# design.net
KiCad netlist of a schematic drawn in Altium Designer
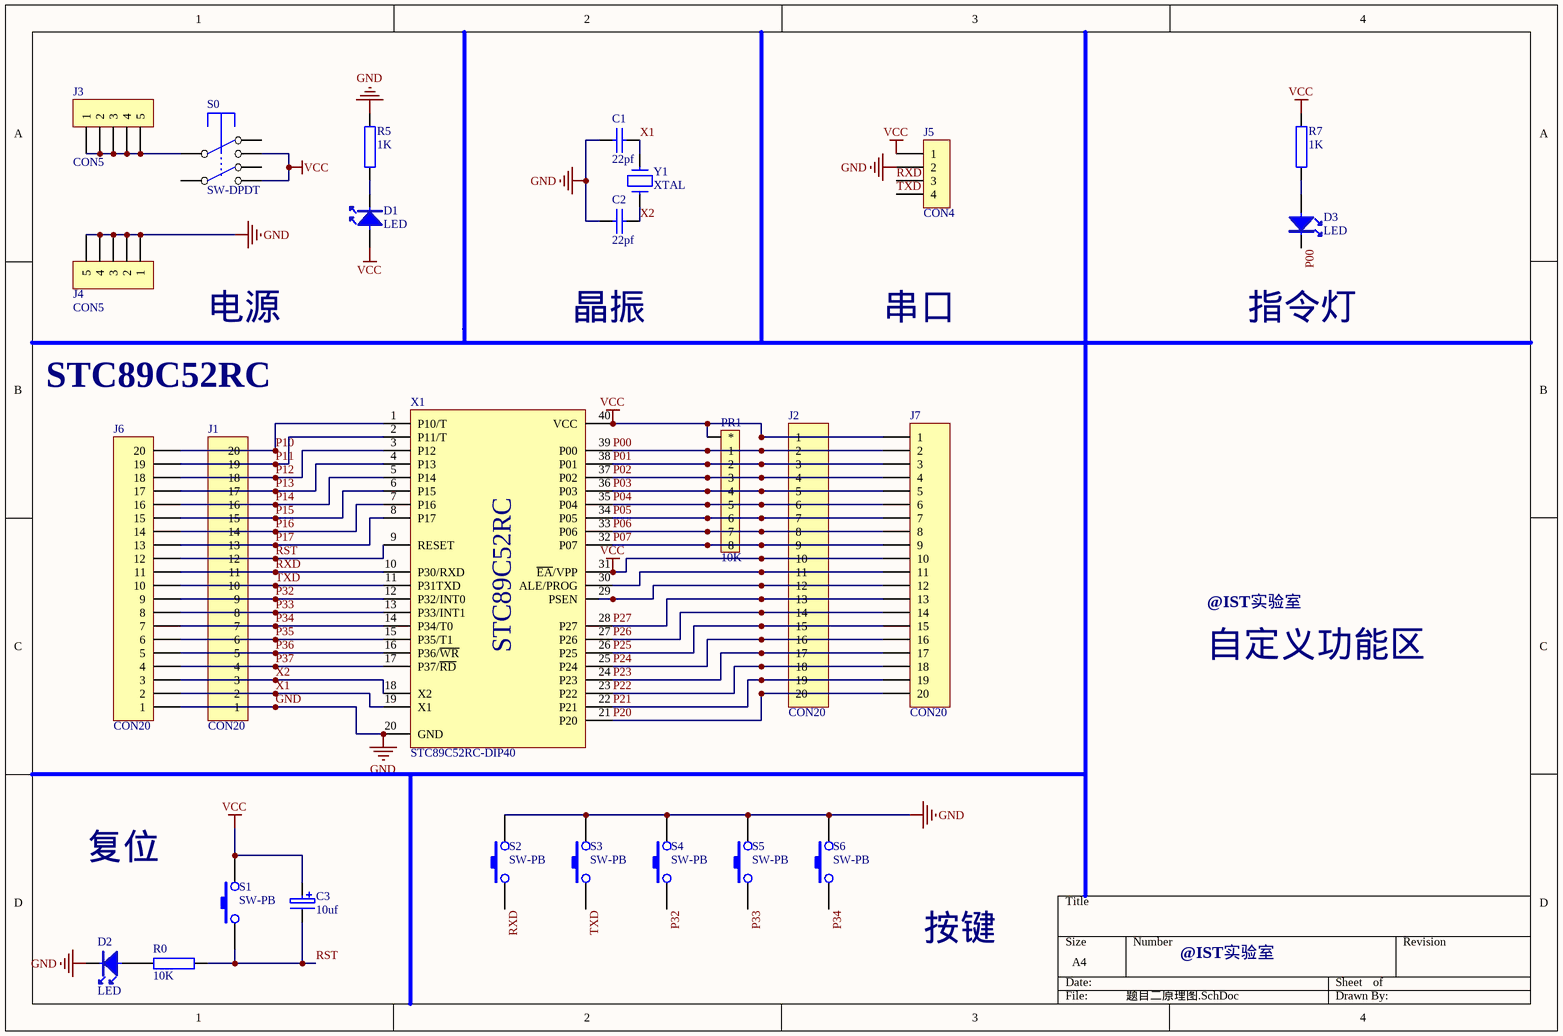
[diagram p0: 题目二原理图.SchDoc]

(export (version "E")
  (design (tool "Eeschema 10.0.6"))
  (components
    (comp (ref "C1") (value "22pf") (footprint "CAP2") (libsource (lib "51单片机集成库") (part "CAP1")))
    (comp (ref "C2") (value "22pf") (footprint "CAP2") (libsource (lib "51单片机集成库") (part "CAP1")))
    (comp (ref "C3") (value "10uf") (footprint "CAO1") (libsource (lib "51单片机集成库") (part "CAP3")))
    (comp (ref "D1") (value "LED") (footprint "LED2_B") (libsource (lib "51单片机集成库") (part "LED")))
    (comp (ref "D2") (value "LED") (footprint "LED2_B") (libsource (lib "51单片机集成库") (part "LED")))
    (comp (ref "D3") (value "LED") (footprint "LED2_B") (libsource (lib "51单片机集成库") (part "LED")))
    (comp (ref "J1")
      (value "CON20")
      (footprint "sip-20")
      (description "Connector")
      (libsource (lib "") (part "CON20_1"))
    )
    (comp (ref "J2")
      (value "CON20")
      (footprint "sip-20")
      (description "Connector")
      (libsource (lib "51单片机集成库") (part "CON20"))
    )
    (comp (ref "J3")
      (value "CON5")
      (footprint "sip-5")
      (description "Connector")
      (libsource (lib "51单片机集成库") (part "CON5"))
    )
    (comp (ref "J4")
      (value "CON5")
      (footprint "sip-5")
      (description "Connector")
      (libsource (lib "") (part "CON5_1"))
    )
    (comp (ref "J5")
      (value "CON4")
      (footprint "sip-4")
      (description "Connector")
      (libsource (lib "51单片机集成库") (part "CON4"))
    )
    (comp (ref "J6")
      (value "CON20")
      (footprint "sip-20")
      (description "Connector")
      (libsource (lib "") (part "CON20_1"))
    )
    (comp (ref "J7")
      (value "CON20")
      (footprint "sip-20")
      (description "Connector")
      (libsource (lib "51单片机集成库") (part "CON20"))
    )
    (comp (ref "PR1") (value "10K") (footprint "RP1") (libsource (lib "51单片机集成库") (part "PRES1")))
    (comp (ref "R0")
      (value "10K")
      (footprint "AXIAL0.4")
      (description "电阻")
      (libsource (lib "51单片机集成库") (part "RES"))
    )
    (comp (ref "R5")
      (value "1K")
      (footprint "AXIAL0.4")
      (description "电阻")
      (libsource (lib "51单片机集成库") (part "RES"))
    )
    (comp (ref "R7")
      (value "1K")
      (footprint "AXIAL0.4")
      (description "电阻")
      (libsource (lib "51单片机集成库") (part "RES"))
    )
    (comp (ref "S0") (value "SW-DPDT") (footprint "SWH7*7") (libsource (lib "51单片机集成库") (part "SW-DPDT")))
    (comp (ref "S1") (value "SW-PB") (footprint "SW6*6") (libsource (lib "51单片机集成库") (part "SW-PB")))
    (comp (ref "S2") (value "SW-PB") (footprint "SW6*6") (libsource (lib "51单片机集成库") (part "SW-PB")))
    (comp (ref "S3") (value "SW-PB") (footprint "SW6*6") (libsource (lib "51单片机集成库") (part "SW-PB")))
    (comp (ref "S4") (value "SW-PB") (footprint "SW6*6") (libsource (lib "51单片机集成库") (part "SW-PB")))
    (comp (ref "S5") (value "SW-PB") (footprint "SW6*6") (libsource (lib "51单片机集成库") (part "SW-PB")))
    (comp (ref "S6") (value "SW-PB") (footprint "SW6*6") (libsource (lib "51单片机集成库") (part "SW-PB")))
    (comp (ref "X1")
      (value "STC89C52RC-DIP40")
      (footprint "DIP-40")
      (libsource (lib "51单片机集成库") (part "STC89C52RC-DIP40"))
    )
    (comp (ref "Y1") (value "XTAL") (footprint "XTAL1") (libsource (lib "51单片机集成库") (part "CPY")))
  )
  (nets
    (net (code "1") (name "/P00") (class "Default")
      (node (ref "D3") (pin "2") (pinfunction "2_2") (pintype "passive"))
      (node (ref "J2") (pin "2") (pinfunction "2_2") (pintype "passive"))
      (node (ref "J7") (pin "2") (pinfunction "2_2") (pintype "passive"))
      (node (ref "PR1") (pin "2") (pinfunction "1_2") (pintype "passive"))
      (node (ref "X1") (pin "39") (pinfunction "P00_39") (pintype "passive"))
    )
    (net (code "2") (name "/P01") (class "Default")
      (node (ref "J2") (pin "3") (pinfunction "3_3") (pintype "passive"))
      (node (ref "J7") (pin "3") (pinfunction "3_3") (pintype "passive"))
      (node (ref "PR1") (pin "3") (pinfunction "2_3") (pintype "passive"))
      (node (ref "X1") (pin "38") (pinfunction "P01_38") (pintype "passive"))
    )
    (net (code "3") (name "/P02") (class "Default")
      (node (ref "J2") (pin "4") (pinfunction "4_4") (pintype "passive"))
      (node (ref "J7") (pin "4") (pinfunction "4_4") (pintype "passive"))
      (node (ref "PR1") (pin "4") (pinfunction "3_4") (pintype "passive"))
      (node (ref "X1") (pin "37") (pinfunction "P02_37") (pintype "passive"))
    )
    (net (code "4") (name "/P03") (class "Default")
      (node (ref "J2") (pin "5") (pinfunction "5_5") (pintype "passive"))
      (node (ref "J7") (pin "5") (pinfunction "5_5") (pintype "passive"))
      (node (ref "PR1") (pin "5") (pinfunction "4_5") (pintype "passive"))
      (node (ref "X1") (pin "36") (pinfunction "P03_36") (pintype "passive"))
    )
    (net (code "5") (name "/P04") (class "Default")
      (node (ref "J2") (pin "6") (pinfunction "6_6") (pintype "passive"))
      (node (ref "J7") (pin "6") (pinfunction "6_6") (pintype "passive"))
      (node (ref "PR1") (pin "6") (pinfunction "5_6") (pintype "passive"))
      (node (ref "X1") (pin "35") (pinfunction "P04_35") (pintype "passive"))
    )
    (net (code "6") (name "/P05") (class "Default")
      (node (ref "J2") (pin "7") (pinfunction "7_7") (pintype "passive"))
      (node (ref "J7") (pin "7") (pinfunction "7_7") (pintype "passive"))
      (node (ref "PR1") (pin "7") (pinfunction "6_7") (pintype "passive"))
      (node (ref "X1") (pin "34") (pinfunction "P05_34") (pintype "passive"))
    )
    (net (code "7") (name "/P06") (class "Default")
      (node (ref "J2") (pin "8") (pinfunction "8_8") (pintype "passive"))
      (node (ref "J7") (pin "8") (pinfunction "8_8") (pintype "passive"))
      (node (ref "PR1") (pin "8") (pinfunction "7_8") (pintype "passive"))
      (node (ref "X1") (pin "33") (pinfunction "P06_33") (pintype "passive"))
    )
    (net (code "8") (name "/P07") (class "Default")
      (node (ref "J2") (pin "9") (pinfunction "9_9") (pintype "passive"))
      (node (ref "J7") (pin "9") (pinfunction "9_9") (pintype "passive"))
      (node (ref "PR1") (pin "9") (pinfunction "8_9") (pintype "passive"))
      (node (ref "X1") (pin "32") (pinfunction "P07_32") (pintype "passive"))
    )
    (net (code "9") (name "/P10") (class "Default")
      (node (ref "J1") (pin "20") (pinfunction "20_20") (pintype "passive"))
      (node (ref "J6") (pin "20") (pinfunction "20_20") (pintype "passive"))
      (node (ref "X1") (pin "1") (pinfunction "P10/T_1") (pintype "passive"))
    )
    (net (code "10") (name "/P11") (class "Default")
      (node (ref "J1") (pin "19") (pinfunction "19_19") (pintype "passive"))
      (node (ref "J6") (pin "19") (pinfunction "19_19") (pintype "passive"))
      (node (ref "X1") (pin "2") (pinfunction "P11/T_2") (pintype "passive"))
    )
    (net (code "11") (name "/P12") (class "Default")
      (node (ref "J1") (pin "18") (pinfunction "18_18") (pintype "passive"))
      (node (ref "J6") (pin "18") (pinfunction "18_18") (pintype "passive"))
      (node (ref "X1") (pin "3") (pinfunction "P12_3") (pintype "passive"))
    )
    (net (code "12") (name "/P13") (class "Default")
      (node (ref "J1") (pin "17") (pinfunction "17_17") (pintype "passive"))
      (node (ref "J6") (pin "17") (pinfunction "17_17") (pintype "passive"))
      (node (ref "X1") (pin "4") (pinfunction "P13_4") (pintype "passive"))
    )
    (net (code "13") (name "/P14") (class "Default")
      (node (ref "J1") (pin "16") (pinfunction "16_16") (pintype "passive"))
      (node (ref "J6") (pin "16") (pinfunction "16_16") (pintype "passive"))
      (node (ref "X1") (pin "5") (pinfunction "P14_5") (pintype "passive"))
    )
    (net (code "14") (name "/P15") (class "Default")
      (node (ref "J1") (pin "15") (pinfunction "15_15") (pintype "passive"))
      (node (ref "J6") (pin "15") (pinfunction "15_15") (pintype "passive"))
      (node (ref "X1") (pin "6") (pinfunction "P15_6") (pintype "passive"))
    )
    (net (code "15") (name "/P16") (class "Default")
      (node (ref "J1") (pin "14") (pinfunction "14_14") (pintype "passive"))
      (node (ref "J6") (pin "14") (pinfunction "14_14") (pintype "passive"))
      (node (ref "X1") (pin "7") (pinfunction "P16_7") (pintype "passive"))
    )
    (net (code "16") (name "/P17") (class "Default")
      (node (ref "J1") (pin "13") (pinfunction "13_13") (pintype "passive"))
      (node (ref "J6") (pin "13") (pinfunction "13_13") (pintype "passive"))
      (node (ref "X1") (pin "8") (pinfunction "P17_8") (pintype "passive"))
    )
    (net (code "17") (name "/P20") (class "Default")
      (node (ref "J2") (pin "20") (pinfunction "20_20") (pintype "passive"))
      (node (ref "J7") (pin "20") (pinfunction "20_20") (pintype "passive"))
      (node (ref "X1") (pin "21") (pinfunction "P20_21") (pintype "passive"))
    )
    (net (code "18") (name "/P21") (class "Default")
      (node (ref "J2") (pin "19") (pinfunction "19_19") (pintype "passive"))
      (node (ref "J7") (pin "19") (pinfunction "19_19") (pintype "passive"))
      (node (ref "X1") (pin "22") (pinfunction "P21_22") (pintype "passive"))
    )
    (net (code "19") (name "/P22") (class "Default")
      (node (ref "J2") (pin "18") (pinfunction "18_18") (pintype "passive"))
      (node (ref "J7") (pin "18") (pinfunction "18_18") (pintype "passive"))
      (node (ref "X1") (pin "23") (pinfunction "P22_23") (pintype "passive"))
    )
    (net (code "20") (name "/P23") (class "Default")
      (node (ref "J2") (pin "17") (pinfunction "17_17") (pintype "passive"))
      (node (ref "J7") (pin "17") (pinfunction "17_17") (pintype "passive"))
      (node (ref "X1") (pin "24") (pinfunction "P23_24") (pintype "passive"))
    )
    (net (code "21") (name "/P24") (class "Default")
      (node (ref "J2") (pin "16") (pinfunction "16_16") (pintype "passive"))
      (node (ref "J7") (pin "16") (pinfunction "16_16") (pintype "passive"))
      (node (ref "X1") (pin "25") (pinfunction "P24_25") (pintype "passive"))
    )
    (net (code "22") (name "/P25") (class "Default")
      (node (ref "J2") (pin "15") (pinfunction "15_15") (pintype "passive"))
      (node (ref "J7") (pin "15") (pinfunction "15_15") (pintype "passive"))
      (node (ref "X1") (pin "26") (pinfunction "P25_26") (pintype "passive"))
    )
    (net (code "23") (name "/P26") (class "Default")
      (node (ref "J2") (pin "14") (pinfunction "14_14") (pintype "passive"))
      (node (ref "J7") (pin "14") (pinfunction "14_14") (pintype "passive"))
      (node (ref "X1") (pin "27") (pinfunction "P26_27") (pintype "passive"))
    )
    (net (code "24") (name "/P27") (class "Default")
      (node (ref "J2") (pin "13") (pinfunction "13_13") (pintype "passive"))
      (node (ref "J7") (pin "13") (pinfunction "13_13") (pintype "passive"))
      (node (ref "X1") (pin "28") (pinfunction "P27_28") (pintype "passive"))
    )
    (net (code "25") (name "/P32") (class "Default")
      (node (ref "J1") (pin "9") (pinfunction "9_9") (pintype "passive"))
      (node (ref "J6") (pin "9") (pinfunction "9_9") (pintype "passive"))
      (node (ref "S4") (pin "1") (pinfunction "1_1") (pintype "passive"))
      (node (ref "X1") (pin "12") (pinfunction "P32/INT0_12") (pintype "passive"))
    )
    (net (code "26") (name "/P33") (class "Default")
      (node (ref "J1") (pin "8") (pinfunction "8_8") (pintype "passive"))
      (node (ref "J6") (pin "8") (pinfunction "8_8") (pintype "passive"))
      (node (ref "S5") (pin "1") (pinfunction "1_1") (pintype "passive"))
      (node (ref "X1") (pin "13") (pinfunction "P33/INT1_13") (pintype "passive"))
    )
    (net (code "27") (name "/P34") (class "Default")
      (node (ref "J1") (pin "7") (pinfunction "7_7") (pintype "passive"))
      (node (ref "J6") (pin "7") (pinfunction "7_7") (pintype "passive"))
      (node (ref "S6") (pin "1") (pinfunction "1_1") (pintype "passive"))
      (node (ref "X1") (pin "14") (pinfunction "P34/T0_14") (pintype "passive"))
    )
    (net (code "28") (name "/P35") (class "Default")
      (node (ref "J1") (pin "6") (pinfunction "6_6") (pintype "passive"))
      (node (ref "J6") (pin "6") (pinfunction "6_6") (pintype "passive"))
      (node (ref "X1") (pin "15") (pinfunction "P35/T1_15") (pintype "passive"))
    )
    (net (code "29") (name "/P36") (class "Default")
      (node (ref "J1") (pin "5") (pinfunction "5_5") (pintype "passive"))
      (node (ref "J6") (pin "5") (pinfunction "5_5") (pintype "passive"))
      (node (ref "X1") (pin "16") (pinfunction "P36/~{WR}_16") (pintype "passive"))
    )
    (net (code "30") (name "/P37") (class "Default")
      (node (ref "J1") (pin "4") (pinfunction "4_4") (pintype "passive"))
      (node (ref "J6") (pin "4") (pinfunction "4_4") (pintype "passive"))
      (node (ref "X1") (pin "17") (pinfunction "P37/~{RD}_17") (pintype "passive"))
    )
    (net (code "31") (name "/RST") (class "Default")
      (node (ref "C3") (pin "2") (pintype "passive"))
      (node (ref "J1") (pin "12") (pinfunction "12_12") (pintype "passive"))
      (node (ref "J6") (pin "12") (pinfunction "12_12") (pintype "passive"))
      (node (ref "R0") (pin "2") (pinfunction "2_2") (pintype "passive"))
      (node (ref "S1") (pin "1") (pinfunction "1_1") (pintype "passive"))
      (node (ref "X1") (pin "9") (pinfunction "RESET_9") (pintype "passive"))
    )
    (net (code "32") (name "/RXD") (class "Default")
      (node (ref "J1") (pin "11") (pinfunction "11_11") (pintype "passive"))
      (node (ref "J5") (pin "3") (pinfunction "3_3") (pintype "passive"))
      (node (ref "J6") (pin "11") (pinfunction "11_11") (pintype "passive"))
      (node (ref "S2") (pin "1") (pinfunction "1_1") (pintype "passive"))
      (node (ref "X1") (pin "10") (pinfunction "P30/RXD_10") (pintype "passive"))
    )
    (net (code "33") (name "/TXD") (class "Default")
      (node (ref "J1") (pin "10") (pinfunction "10_10") (pintype "passive"))
      (node (ref "J5") (pin "4") (pinfunction "4_4") (pintype "passive"))
      (node (ref "J6") (pin "10") (pinfunction "10_10") (pintype "passive"))
      (node (ref "S3") (pin "1") (pinfunction "1_1") (pintype "passive"))
      (node (ref "X1") (pin "11") (pinfunction "P31TXD_11") (pintype "passive"))
    )
    (net (code "34") (name "/X1") (class "Default")
      (node (ref "C1") (pin "1") (pinfunction "1_1") (pintype "passive"))
      (node (ref "J1") (pin "2") (pinfunction "2_2") (pintype "passive"))
      (node (ref "J6") (pin "2") (pinfunction "2_2") (pintype "passive"))
      (node (ref "X1") (pin "19") (pinfunction "X1_19") (pintype "passive"))
      (node (ref "Y1") (pin "2") (pintype "passive"))
    )
    (net (code "35") (name "/X2") (class "Default")
      (node (ref "C2") (pin "1") (pinfunction "1_1") (pintype "passive"))
      (node (ref "J1") (pin "3") (pinfunction "3_3") (pintype "passive"))
      (node (ref "J6") (pin "3") (pinfunction "3_3") (pintype "passive"))
      (node (ref "X1") (pin "18") (pinfunction "X2_18") (pintype "passive"))
      (node (ref "Y1") (pin "1") (pintype "passive"))
    )
    (net (code "36") (name "GND") (class "Default")
      (node (ref "C1") (pin "2") (pinfunction "2_2") (pintype "passive"))
      (node (ref "C2") (pin "2") (pinfunction "2_2") (pintype "passive"))
      (node (ref "D2") (pin "2") (pinfunction "2_2") (pintype "passive"))
      (node (ref "J1") (pin "1") (pinfunction "1_1") (pintype "passive"))
      (node (ref "J4") (pin "1") (pinfunction "1_1") (pintype "passive"))
      (node (ref "J4") (pin "2") (pinfunction "2_2") (pintype "passive"))
      (node (ref "J4") (pin "3") (pinfunction "3_3") (pintype "passive"))
      (node (ref "J4") (pin "4") (pinfunction "4_4") (pintype "passive"))
      (node (ref "J4") (pin "5") (pinfunction "5_5") (pintype "passive"))
      (node (ref "J5") (pin "2") (pinfunction "2_2") (pintype "passive"))
      (node (ref "J6") (pin "1") (pinfunction "1_1") (pintype "passive"))
      (node (ref "R5") (pin "2") (pinfunction "2_2") (pintype "passive"))
      (node (ref "S2") (pin "2") (pinfunction "2_2") (pintype "passive"))
      (node (ref "S3") (pin "2") (pinfunction "2_2") (pintype "passive"))
      (node (ref "S4") (pin "2") (pinfunction "2_2") (pintype "passive"))
      (node (ref "S5") (pin "2") (pinfunction "2_2") (pintype "passive"))
      (node (ref "S6") (pin "2") (pinfunction "2_2") (pintype "passive"))
      (node (ref "X1") (pin "20") (pinfunction "GND_20") (pintype "passive"))
    )
    (net (code "37") (name "Net-(D1-Pad2)") (class "Default")
      (node (ref "D1") (pin "2") (pinfunction "2_2") (pintype "passive"))
      (node (ref "R5") (pin "1") (pinfunction "1_1") (pintype "passive"))
    )
    (net (code "38") (name "Net-(D2-Pad1)") (class "Default")
      (node (ref "D2") (pin "1") (pinfunction "1_1") (pintype "passive"))
      (node (ref "R0") (pin "1") (pinfunction "1_1") (pintype "passive"))
    )
    (net (code "39") (name "Net-(D3-Pad1)") (class "Default")
      (node (ref "D3") (pin "1") (pinfunction "1_1") (pintype "passive"))
      (node (ref "R7") (pin "1") (pinfunction "1_1") (pintype "passive"))
    )
    (net (code "40") (name "Net-(J3-Pad1)") (class "Default")
      (node (ref "J3") (pin "1") (pinfunction "1_1") (pintype "passive"))
      (node (ref "J3") (pin "2") (pinfunction "2_2") (pintype "passive"))
      (node (ref "J3") (pin "3") (pinfunction "3_3") (pintype "passive"))
      (node (ref "J3") (pin "4") (pinfunction "4_4") (pintype "passive"))
      (node (ref "J3") (pin "5") (pinfunction "5_5") (pintype "passive"))
      (node (ref "S0") (pin "2") (pinfunction "2_2") (pintype "passive"))
    )
    (net (code "41") (name "Net-(X1-ALE{slash}PROG)") (class "Default")
      (node (ref "J2") (pin "11") (pinfunction "11_11") (pintype "passive"))
      (node (ref "J7") (pin "11") (pinfunction "11_11") (pintype "passive"))
      (node (ref "X1") (pin "30") (pinfunction "ALE/PROG_30") (pintype "passive"))
    )
    (net (code "42") (name "Net-(X1-PSEN)") (class "Default")
      (node (ref "J2") (pin "12") (pinfunction "12_12") (pintype "passive"))
      (node (ref "J7") (pin "12") (pinfunction "12_12") (pintype "passive"))
      (node (ref "X1") (pin "29") (pinfunction "PSEN_29") (pintype "passive"))
    )
    (net (code "43") (name "VCC") (class "Default")
      (node (ref "C3") (pin "1") (pintype "passive"))
      (node (ref "D1") (pin "1") (pinfunction "1_1") (pintype "passive"))
      (node (ref "J2") (pin "1") (pinfunction "1_1") (pintype "passive"))
      (node (ref "J2") (pin "10") (pinfunction "10_10") (pintype "passive"))
      (node (ref "J5") (pin "1") (pinfunction "1_1") (pintype "passive"))
      (node (ref "J7") (pin "1") (pinfunction "1_1") (pintype "passive"))
      (node (ref "J7") (pin "10") (pinfunction "10_10") (pintype "passive"))
      (node (ref "PR1") (pin "1") (pinfunction "*_1") (pintype "passive"))
      (node (ref "R7") (pin "2") (pinfunction "2_2") (pintype "passive"))
      (node (ref "S0") (pin "3") (pinfunction "3_3") (pintype "passive"))
      (node (ref "S0") (pin "4") (pinfunction "4_4") (pintype "passive"))
      (node (ref "S1") (pin "2") (pinfunction "2_2") (pintype "passive"))
      (node (ref "X1") (pin "31") (pinfunction "~{EA}/VPP_31") (pintype "passive"))
      (node (ref "X1") (pin "40") (pinfunction "VCC_40") (pintype "passive"))
    )
    (net (code "44") (name "unconnected-(S0-Pad1)") (class "Default")
      (node (ref "S0") (pin "1") (pinfunction "1_1") (pintype "passive"))
    )
    (net (code "45") (name "unconnected-(S0-Pad5)") (class "Default")
      (node (ref "S0") (pin "5") (pinfunction "5_5") (pintype "passive"))
    )
    (net (code "46") (name "unconnected-(S0-Pad6)") (class "Default")
      (node (ref "S0") (pin "6") (pinfunction "6_6") (pintype "passive"))
    )
  )
)
